# Ngu_nghiep.net
KiCad netlist of a schematic drawn in Altium Designer
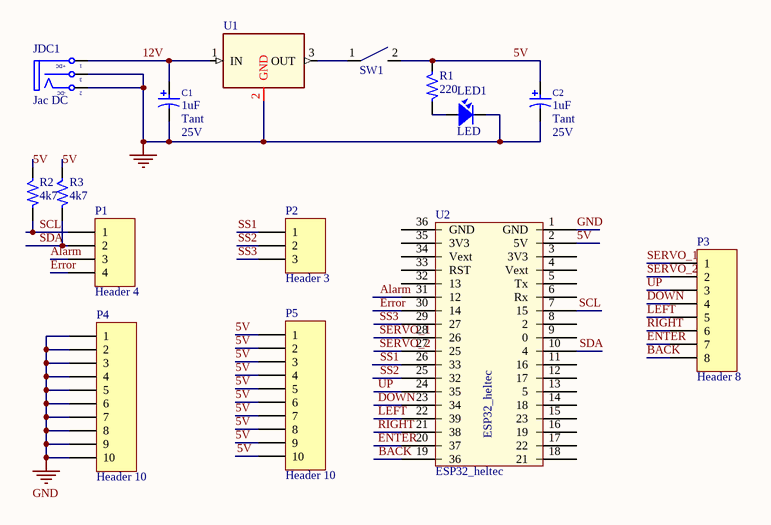
[diagram p0: Ngu nghiep.SchDoc]

(export (version "E")
  (design (tool "Eeschema 10.0.6"))
  (components
    (comp (ref "C1")
      (value "1uF")
      (footprint "RADIAL B")
      (description "Polarized Capacitor")
      (fields
        (field (name "MANUFACTURER") "FARNELL")
        (field (name "CAPACITOR TYPE") "Tant")
        (field (name "VOLT") "25V")
        (field (name "PUBLISHER") "Hoang Nguyen")
      )
      (libsource (lib "hphonglib") (part "Cap_Pol"))
    )
    (comp (ref "C2")
      (value "1uF")
      (footprint "RADIAL B")
      (description "Polarized Capacitor")
      (fields
        (field (name "MANUFACTURER") "FARNELL")
        (field (name "CAPACITOR TYPE") "Tant")
        (field (name "VOLT") "25V")
        (field (name "PUBLISHER") "Hoang Nguyen")
      )
      (libsource (lib "hphonglib") (part "Cap_Pol"))
    )
    (comp (ref "JDC1")
      (value "Jac DC")
      (footprint "DC0")
      (description "Jac DC input")
      (libsource (lib "Library") (part "DCIN"))
    )
    (comp (ref "LED1")
      (value "LED")
      (footprint "LED-5-RED")
      (description "LED Single colour Green and Red")
      (libsource (lib "syhaunguyen") (part "LED"))
    )
    (comp (ref "P1")
      (value "Header 4")
      (footprint "HDR1X4")
      (description "Header, 4-Pin")
      (fields (field (name "PUBLISHER") "Altium Limited"))
      (libsource (lib "My Library") (part "Header 4"))
    )
    (comp (ref "P2")
      (value "Header 3")
      (footprint "HDR1X3")
      (description "Header, 3-Pin")
      (fields (field (name "PUBLISHER") "Altium Limited"))
      (libsource (lib "My Library") (part "Header 3"))
    )
    (comp (ref "P3")
      (value "Header 8")
      (footprint "HDR1X8")
      (description "Header, 8-Pin")
      (fields (field (name "PUBLISHER") "Altium Limited"))
      (libsource (lib "My Library") (part "Header 8"))
    )
    (comp (ref "P4")
      (value "Header 10")
      (footprint "HDR1X10")
      (description "Header, 10-Pin")
      (fields (field (name "PUBLISHER") "Altium Limited"))
      (libsource (lib "My Library") (part "Header 10"))
    )
    (comp (ref "P5")
      (value "Header 10")
      (footprint "HDR1X10")
      (description "Header, 10-Pin")
      (fields (field (name "PUBLISHER") "Altium Limited"))
      (libsource (lib "My Library") (part "Header 10"))
    )
    (comp (ref "R1")
      (value "220")
      (footprint "RES-1/4W")
      (description "Resistor 1/4W")
      (libsource (lib "syhaunguyen") (part "R"))
    )
    (comp (ref "R2")
      (value "4k7")
      (footprint "RES-1/4W")
      (description "Resistor 1/4W")
      (libsource (lib "syhaunguyen") (part "R"))
    )
    (comp (ref "R3")
      (value "4k7")
      (footprint "RES-1/4W")
      (description "Resistor 1/4W")
      (libsource (lib "syhaunguyen") (part "R"))
    )
    (comp (ref "SW1")
      (value "SW 2_BAP BENH_MH")
      (footprint "MH_DA_THU_VIEN_16122016:SW2_ BAP BENH")
      (description "Công tắc bập bênh 2 chân MH001568")
      (libsource (lib "MH_DA_THU_VIEN_16122016") (part "SW 2_BAP BENH_MH"))
    )
    (comp (ref "U1")
      (value "LM78xx")
      (footprint "TO-220")
      (description "Regulator")
      (fields
        (field (name "MANUFACTURER") "Fairchild Semiconductor Corporation")
        (field (name "TOLERANCE") "4 %")
        (field (name "PUBLISHER") "Hoang Nguyen")
      )
      (libsource (lib "hphonglib") (part "LM78xx"))
    )
    (comp (ref "U2")
      (value "ESP32_heltec")
      (footprint "ESP32_WFK_Heltec")
      (description "ESP32 IOT kit")
      (libsource (lib "MinhTien_SCHLib") (part "ESP32_heltec"))
    )
  )
  (nets
    (net (code "1") (name "/5V") (class "Default")
      (node (ref "C2") (pin "1") (pinfunction "1_1") (pintype "passive"))
      (node (ref "P5") (pin "1") (pinfunction "1_1") (pintype "passive"))
      (node (ref "P5") (pin "10") (pinfunction "10_10") (pintype "passive"))
      (node (ref "P5") (pin "2") (pinfunction "2_2") (pintype "passive"))
      (node (ref "P5") (pin "3") (pinfunction "3_3") (pintype "passive"))
      (node (ref "P5") (pin "4") (pinfunction "4_4") (pintype "passive"))
      (node (ref "P5") (pin "5") (pinfunction "5_5") (pintype "passive"))
      (node (ref "P5") (pin "6") (pinfunction "6_6") (pintype "passive"))
      (node (ref "P5") (pin "7") (pinfunction "7_7") (pintype "passive"))
      (node (ref "P5") (pin "8") (pinfunction "8_8") (pintype "passive"))
      (node (ref "P5") (pin "9") (pinfunction "9_9") (pintype "passive"))
      (node (ref "R1") (pin "1") (pinfunction "1_1") (pintype "passive"))
      (node (ref "R2") (pin "1") (pinfunction "1_1") (pintype "passive"))
      (node (ref "R3") (pin "1") (pinfunction "1_1") (pintype "passive"))
      (node (ref "SW1") (pin "2") (pintype "passive"))
      (node (ref "U2") (pin "2") (pinfunction "5V_2") (pintype "passive"))
    )
    (net (code "2") (name "/12V") (class "Default")
      (node (ref "C1") (pin "1") (pinfunction "1_1") (pintype "passive"))
      (node (ref "JDC1") (pin "1") (pinfunction "T_1") (pintype "passive"))
      (node (ref "U1") (pin "1") (pinfunction "IN_1") (pintype "input"))
    )
    (net (code "3") (name "/Alarm") (class "Default")
      (node (ref "P1") (pin "3") (pinfunction "3_3") (pintype "passive"))
      (node (ref "U2") (pin "31") (pinfunction "12_31") (pintype "passive"))
    )
    (net (code "4") (name "/BACK") (class "Default")
      (node (ref "P3") (pin "8") (pinfunction "8_8") (pintype "passive"))
      (node (ref "U2") (pin "19") (pinfunction "36_19") (pintype "passive"))
    )
    (net (code "5") (name "/DOWN") (class "Default")
      (node (ref "P3") (pin "4") (pinfunction "4_4") (pintype "passive"))
      (node (ref "U2") (pin "23") (pinfunction "34_23") (pintype "passive"))
    )
    (net (code "6") (name "/ENTER") (class "Default")
      (node (ref "P3") (pin "7") (pinfunction "7_7") (pintype "passive"))
      (node (ref "U2") (pin "20") (pinfunction "37_20") (pintype "passive"))
    )
    (net (code "7") (name "/Error") (class "Default")
      (node (ref "P1") (pin "4") (pinfunction "4_4") (pintype "passive"))
      (node (ref "U2") (pin "30") (pinfunction "14_30") (pintype "passive"))
    )
    (net (code "8") (name "/LEFT") (class "Default")
      (node (ref "P3") (pin "5") (pinfunction "5_5") (pintype "passive"))
      (node (ref "U2") (pin "22") (pinfunction "39_22") (pintype "passive"))
    )
    (net (code "9") (name "/RIGHT") (class "Default")
      (node (ref "P3") (pin "6") (pinfunction "6_6") (pintype "passive"))
      (node (ref "U2") (pin "21") (pinfunction "38_21") (pintype "passive"))
    )
    (net (code "10") (name "/SCL") (class "Default")
      (node (ref "P1") (pin "1") (pinfunction "1_1") (pintype "passive"))
      (node (ref "R2") (pin "2") (pinfunction "2_2") (pintype "passive"))
      (node (ref "U2") (pin "7") (pinfunction "15_7") (pintype "passive"))
    )
    (net (code "11") (name "/SDA") (class "Default")
      (node (ref "P1") (pin "2") (pinfunction "2_2") (pintype "passive"))
      (node (ref "R3") (pin "2") (pinfunction "2_2") (pintype "passive"))
      (node (ref "U2") (pin "10") (pinfunction "4_10") (pintype "passive"))
    )
    (net (code "12") (name "/SERVO_1") (class "Default")
      (node (ref "P3") (pin "1") (pinfunction "1_1") (pintype "passive"))
      (node (ref "U2") (pin "28") (pinfunction "26_28") (pintype "passive"))
    )
    (net (code "13") (name "/SERVO_2") (class "Default")
      (node (ref "P3") (pin "2") (pinfunction "2_2") (pintype "passive"))
      (node (ref "U2") (pin "27") (pinfunction "25_27") (pintype "passive"))
    )
    (net (code "14") (name "/SS1") (class "Default")
      (node (ref "P2") (pin "1") (pinfunction "1_1") (pintype "passive"))
      (node (ref "U2") (pin "26") (pinfunction "33_26") (pintype "passive"))
    )
    (net (code "15") (name "/SS2") (class "Default")
      (node (ref "P2") (pin "2") (pinfunction "2_2") (pintype "passive"))
      (node (ref "U2") (pin "25") (pinfunction "32_25") (pintype "passive"))
    )
    (net (code "16") (name "/SS3") (class "Default")
      (node (ref "P2") (pin "3") (pinfunction "3_3") (pintype "passive"))
      (node (ref "U2") (pin "29") (pinfunction "27_29") (pintype "passive"))
    )
    (net (code "17") (name "/UP") (class "Default")
      (node (ref "P3") (pin "3") (pinfunction "3_3") (pintype "passive"))
      (node (ref "U2") (pin "24") (pinfunction "35_24") (pintype "passive"))
    )
    (net (code "18") (name "GND") (class "Default")
      (node (ref "C1") (pin "2") (pinfunction "2_2") (pintype "passive"))
      (node (ref "C2") (pin "2") (pinfunction "2_2") (pintype "passive"))
      (node (ref "JDC1") (pin "2") (pinfunction "TN_2") (pintype "passive"))
      (node (ref "JDC1") (pin "3") (pinfunction "S_3") (pintype "power_in"))
      (node (ref "LED1") (pin "2") (pinfunction "2_2") (pintype "passive"))
      (node (ref "P4") (pin "1") (pinfunction "1_1") (pintype "passive"))
      (node (ref "P4") (pin "10") (pinfunction "10_10") (pintype "passive"))
      (node (ref "P4") (pin "2") (pinfunction "2_2") (pintype "passive"))
      (node (ref "P4") (pin "3") (pinfunction "3_3") (pintype "passive"))
      (node (ref "P4") (pin "4") (pinfunction "4_4") (pintype "passive"))
      (node (ref "P4") (pin "5") (pinfunction "5_5") (pintype "passive"))
      (node (ref "P4") (pin "6") (pinfunction "6_6") (pintype "passive"))
      (node (ref "P4") (pin "7") (pinfunction "7_7") (pintype "passive"))
      (node (ref "P4") (pin "8") (pinfunction "8_8") (pintype "passive"))
      (node (ref "P4") (pin "9") (pinfunction "9_9") (pintype "passive"))
      (node (ref "U1") (pin "2") (pinfunction "GND_2") (pintype "power_in"))
      (node (ref "U2") (pin "1") (pinfunction "GND_1") (pintype "passive"))
    )
    (net (code "19") (name "Net-(LED1-Pad1)") (class "Default")
      (node (ref "LED1") (pin "1") (pinfunction "1_1") (pintype "passive"))
      (node (ref "R1") (pin "2") (pinfunction "2_2") (pintype "passive"))
    )
    (net (code "20") (name "Net-(U1-OUT)") (class "Default")
      (node (ref "SW1") (pin "1") (pintype "passive"))
      (node (ref "U1") (pin "3") (pinfunction "OUT_3") (pintype "output"))
    )
    (net (code "21") (name "unconnected-(U2-0-Pad9)") (class "Default")
      (node (ref "U2") (pin "9") (pinfunction "0_9") (pintype "passive"))
    )
    (net (code "22") (name "unconnected-(U2-2-Pad8)") (class "Default")
      (node (ref "U2") (pin "8") (pinfunction "2_8") (pintype "passive"))
    )
    (net (code "23") (name "unconnected-(U2-3V3-Pad3)") (class "Default")
      (node (ref "U2") (pin "3") (pinfunction "3V3_3") (pintype "passive"))
    )
    (net (code "24") (name "unconnected-(U2-3V3-Pad35)") (class "Default")
      (node (ref "U2") (pin "35") (pinfunction "3V3_35") (pintype "passive"))
    )
    (net (code "25") (name "unconnected-(U2-5-Pad13)") (class "Default")
      (node (ref "U2") (pin "13") (pinfunction "5_13") (pintype "passive"))
    )
    (net (code "26") (name "unconnected-(U2-13-Pad32)") (class "Default")
      (node (ref "U2") (pin "32") (pinfunction "13_32") (pintype "passive"))
    )
    (net (code "27") (name "unconnected-(U2-16-Pad11)") (class "Default")
      (node (ref "U2") (pin "11") (pinfunction "16_11") (pintype "passive"))
    )
    (net (code "28") (name "unconnected-(U2-17-Pad12)") (class "Default")
      (node (ref "U2") (pin "12") (pinfunction "17_12") (pintype "passive"))
    )
    (net (code "29") (name "unconnected-(U2-18-Pad14)") (class "Default")
      (node (ref "U2") (pin "14") (pinfunction "18_14") (pintype "passive"))
    )
    (net (code "30") (name "unconnected-(U2-19-Pad16)") (class "Default")
      (node (ref "U2") (pin "16") (pinfunction "19_16") (pintype "passive"))
    )
    (net (code "31") (name "unconnected-(U2-21-Pad18)") (class "Default")
      (node (ref "U2") (pin "18") (pinfunction "21_18") (pintype "passive"))
    )
    (net (code "32") (name "unconnected-(U2-22-Pad17)") (class "Default")
      (node (ref "U2") (pin "17") (pinfunction "22_17") (pintype "passive"))
    )
    (net (code "33") (name "unconnected-(U2-23-Pad15)") (class "Default")
      (node (ref "U2") (pin "15") (pinfunction "23_15") (pintype "passive"))
    )
    (net (code "34") (name "unconnected-(U2-GND-Pad36)") (class "Default")
      (node (ref "U2") (pin "36") (pinfunction "GND_36") (pintype "passive"))
    )
    (net (code "35") (name "unconnected-(U2-RST-Pad33)") (class "Default")
      (node (ref "U2") (pin "33") (pinfunction "RST_33") (pintype "passive"))
    )
    (net (code "36") (name "unconnected-(U2-Rx-Pad6)") (class "Default")
      (node (ref "U2") (pin "6") (pinfunction "Rx_6") (pintype "passive"))
    )
    (net (code "37") (name "unconnected-(U2-Tx-Pad5)") (class "Default")
      (node (ref "U2") (pin "5") (pinfunction "Tx_5") (pintype "passive"))
    )
    (net (code "38") (name "unconnected-(U2-Vext-Pad4)") (class "Default")
      (node (ref "U2") (pin "4") (pinfunction "Vext_4") (pintype "passive"))
    )
    (net (code "39") (name "unconnected-(U2-Vext-Pad34)") (class "Default")
      (node (ref "U2") (pin "34") (pinfunction "Vext_34") (pintype "passive"))
    )
  )
)
